# Connector.net
KiCad netlist of a schematic drawn in Altium Designer
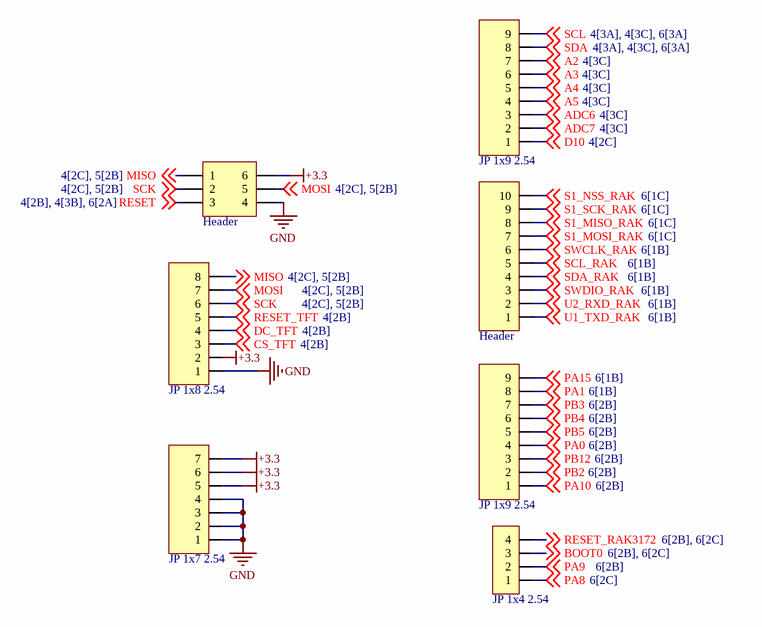
[diagram p0: Connector.SchDoc]

(export (version "E")
  (design (tool "Eeschema 10.0.6"))
  (components
    (comp (ref "JP1")
      (value "JP 1x9 2.54")
      (footprint "JP 1x9 CT")
      (description "Cắm")
      (libsource (lib "Jump") (part "JP 1x9 2.54 Cai Thang"))
    )
    (comp (ref "JP2")
      (value "Header")
      (footprint "JP 2x3 DT")
      (description "Cắm")
      (libsource (lib "Jump") (part "JP 2x3 2.54 Duc Thang"))
    )
    (comp (ref "JP3")
      (value "Header")
      (footprint "JP 1x10 CT")
      (description "Cắm")
      (libsource (lib "Jump") (part "JP 1x10 2.54 Cai Thang"))
    )
    (comp (ref "JP4")
      (value "JP 1x8 2.54")
      (footprint "JP 1x8 CT")
      (description "Cắm")
      (libsource (lib "Jump") (part "JP 1x8 2.54 Cai Thang"))
    )
    (comp (ref "JP5")
      (value "JP 1x9 2.54")
      (footprint "JP 1x9 CT")
      (description "Cắm")
      (libsource (lib "Jump") (part "JP 1x9 2.54 Cai Thang"))
    )
    (comp (ref "JP6")
      (value "JP 1x7 2.54")
      (footprint "JP 1x7 CT")
      (description "Cắm")
      (libsource (lib "Jump") (part "JP 1x7 2.54 Cai Thang"))
    )
    (comp (ref "JP7")
      (value "JP 1x4 2.54")
      (footprint "JP 1x4 CT")
      (description "Cắm")
      (libsource (lib "Jump") (part "JP 1x4 2.54 Cai Thang"))
    )
  )
  (nets
    (net (code "1") (name "+3.3") (class "Default")
      (node (ref "JP2") (pin "6") (pinfunction "6_6") (pintype "passive"))
      (node (ref "JP4") (pin "2") (pinfunction "2_2") (pintype "passive"))
      (node (ref "JP6") (pin "5") (pinfunction "5_5") (pintype "passive"))
      (node (ref "JP6") (pin "6") (pinfunction "6_6") (pintype "passive"))
      (node (ref "JP6") (pin "7") (pinfunction "7_7") (pintype "passive"))
    )
    (net (code "2") (name "A2") (class "Default")
      (node (ref "JP1") (pin "7") (pinfunction "7_7") (pintype "passive"))
    )
    (net (code "3") (name "A3") (class "Default")
      (node (ref "JP1") (pin "6") (pinfunction "6_6") (pintype "passive"))
    )
    (net (code "4") (name "A4") (class "Default")
      (node (ref "JP1") (pin "5") (pinfunction "5_5") (pintype "passive"))
    )
    (net (code "5") (name "A5") (class "Default")
      (node (ref "JP1") (pin "4") (pinfunction "4_4") (pintype "passive"))
    )
    (net (code "6") (name "ADC6") (class "Default")
      (node (ref "JP1") (pin "3") (pinfunction "3_3") (pintype "passive"))
    )
    (net (code "7") (name "ADC7") (class "Default")
      (node (ref "JP1") (pin "2") (pinfunction "2_2") (pintype "passive"))
    )
    (net (code "8") (name "BOOT0") (class "Default")
      (node (ref "JP7") (pin "3") (pinfunction "3_3") (pintype "passive"))
    )
    (net (code "9") (name "CS_TFT") (class "Default")
      (node (ref "JP4") (pin "3") (pinfunction "3_3") (pintype "passive"))
    )
    (net (code "10") (name "D10") (class "Default")
      (node (ref "JP1") (pin "1") (pinfunction "1_1") (pintype "passive"))
    )
    (net (code "11") (name "DC_TFT") (class "Default")
      (node (ref "JP4") (pin "4") (pinfunction "4_4") (pintype "passive"))
    )
    (net (code "12") (name "GND") (class "Default")
      (node (ref "JP2") (pin "4") (pinfunction "4_4") (pintype "passive"))
      (node (ref "JP4") (pin "1") (pinfunction "1_1") (pintype "passive"))
      (node (ref "JP6") (pin "1") (pinfunction "1_1") (pintype "passive"))
      (node (ref "JP6") (pin "2") (pinfunction "2_2") (pintype "passive"))
      (node (ref "JP6") (pin "3") (pinfunction "3_3") (pintype "passive"))
      (node (ref "JP6") (pin "4") (pinfunction "4_4") (pintype "passive"))
    )
    (net (code "13") (name "MISO") (class "Default")
      (node (ref "JP2") (pin "1") (pinfunction "1_1") (pintype "passive"))
      (node (ref "JP4") (pin "8") (pinfunction "8_8") (pintype "passive"))
    )
    (net (code "14") (name "MOSI") (class "Default")
      (node (ref "JP2") (pin "5") (pinfunction "5_5") (pintype "passive"))
      (node (ref "JP4") (pin "7") (pinfunction "7_7") (pintype "passive"))
    )
    (net (code "15") (name "PA0") (class "Default")
      (node (ref "JP5") (pin "4") (pinfunction "4_4") (pintype "passive"))
    )
    (net (code "16") (name "PA1") (class "Default")
      (node (ref "JP5") (pin "8") (pinfunction "8_8") (pintype "passive"))
    )
    (net (code "17") (name "PA8") (class "Default")
      (node (ref "JP7") (pin "1") (pinfunction "1_1") (pintype "passive"))
    )
    (net (code "18") (name "PA9") (class "Default")
      (node (ref "JP7") (pin "2") (pinfunction "2_2") (pintype "passive"))
    )
    (net (code "19") (name "PA10") (class "Default")
      (node (ref "JP5") (pin "1") (pinfunction "1_1") (pintype "passive"))
    )
    (net (code "20") (name "PA15") (class "Default")
      (node (ref "JP5") (pin "9") (pinfunction "9_9") (pintype "passive"))
    )
    (net (code "21") (name "PB2") (class "Default")
      (node (ref "JP5") (pin "2") (pinfunction "2_2") (pintype "passive"))
    )
    (net (code "22") (name "PB3") (class "Default")
      (node (ref "JP5") (pin "7") (pinfunction "7_7") (pintype "passive"))
    )
    (net (code "23") (name "PB4") (class "Default")
      (node (ref "JP5") (pin "6") (pinfunction "6_6") (pintype "passive"))
    )
    (net (code "24") (name "PB5") (class "Default")
      (node (ref "JP5") (pin "5") (pinfunction "5_5") (pintype "passive"))
    )
    (net (code "25") (name "PB12") (class "Default")
      (node (ref "JP5") (pin "3") (pinfunction "3_3") (pintype "passive"))
    )
    (net (code "26") (name "RESET") (class "Default")
      (node (ref "JP2") (pin "3") (pinfunction "3_3") (pintype "passive"))
    )
    (net (code "27") (name "RESET_RAK3172") (class "Default")
      (node (ref "JP7") (pin "4") (pinfunction "4_4") (pintype "passive"))
    )
    (net (code "28") (name "RESET_TFT") (class "Default")
      (node (ref "JP4") (pin "5") (pinfunction "5_5") (pintype "passive"))
    )
    (net (code "29") (name "S1_MISO_RAK") (class "Default")
      (node (ref "JP3") (pin "8") (pinfunction "8_8") (pintype "passive"))
    )
    (net (code "30") (name "S1_MOSI_RAK") (class "Default")
      (node (ref "JP3") (pin "7") (pinfunction "7_7") (pintype "passive"))
    )
    (net (code "31") (name "S1_NSS_RAK") (class "Default")
      (node (ref "JP3") (pin "10") (pinfunction "10_10") (pintype "passive"))
    )
    (net (code "32") (name "S1_SCK_RAK") (class "Default")
      (node (ref "JP3") (pin "9") (pinfunction "9_9") (pintype "passive"))
    )
    (net (code "33") (name "SCK") (class "Default")
      (node (ref "JP2") (pin "2") (pinfunction "2_2") (pintype "passive"))
      (node (ref "JP4") (pin "6") (pinfunction "6_6") (pintype "passive"))
    )
    (net (code "34") (name "SCL") (class "Default")
      (node (ref "JP1") (pin "9") (pinfunction "9_9") (pintype "passive"))
    )
    (net (code "35") (name "SCL_RAK") (class "Default")
      (node (ref "JP3") (pin "5") (pinfunction "5_5") (pintype "passive"))
    )
    (net (code "36") (name "SDA") (class "Default")
      (node (ref "JP1") (pin "8") (pinfunction "8_8") (pintype "passive"))
    )
    (net (code "37") (name "SDA_RAK") (class "Default")
      (node (ref "JP3") (pin "4") (pinfunction "4_4") (pintype "passive"))
    )
    (net (code "38") (name "SWCLK_RAK") (class "Default")
      (node (ref "JP3") (pin "6") (pinfunction "6_6") (pintype "passive"))
    )
    (net (code "39") (name "SWDIO_RAK") (class "Default")
      (node (ref "JP3") (pin "3") (pinfunction "3_3") (pintype "passive"))
    )
    (net (code "40") (name "U1_TXD_RAK") (class "Default")
      (node (ref "JP3") (pin "1") (pinfunction "1_1") (pintype "passive"))
    )
    (net (code "41") (name "U2_RXD_RAK") (class "Default")
      (node (ref "JP3") (pin "2") (pinfunction "2_2") (pintype "passive"))
    )
  )
)
